# Sharp_IR_Distance_2YA02.net
KiCad netlist of a schematic drawn in EAGLE
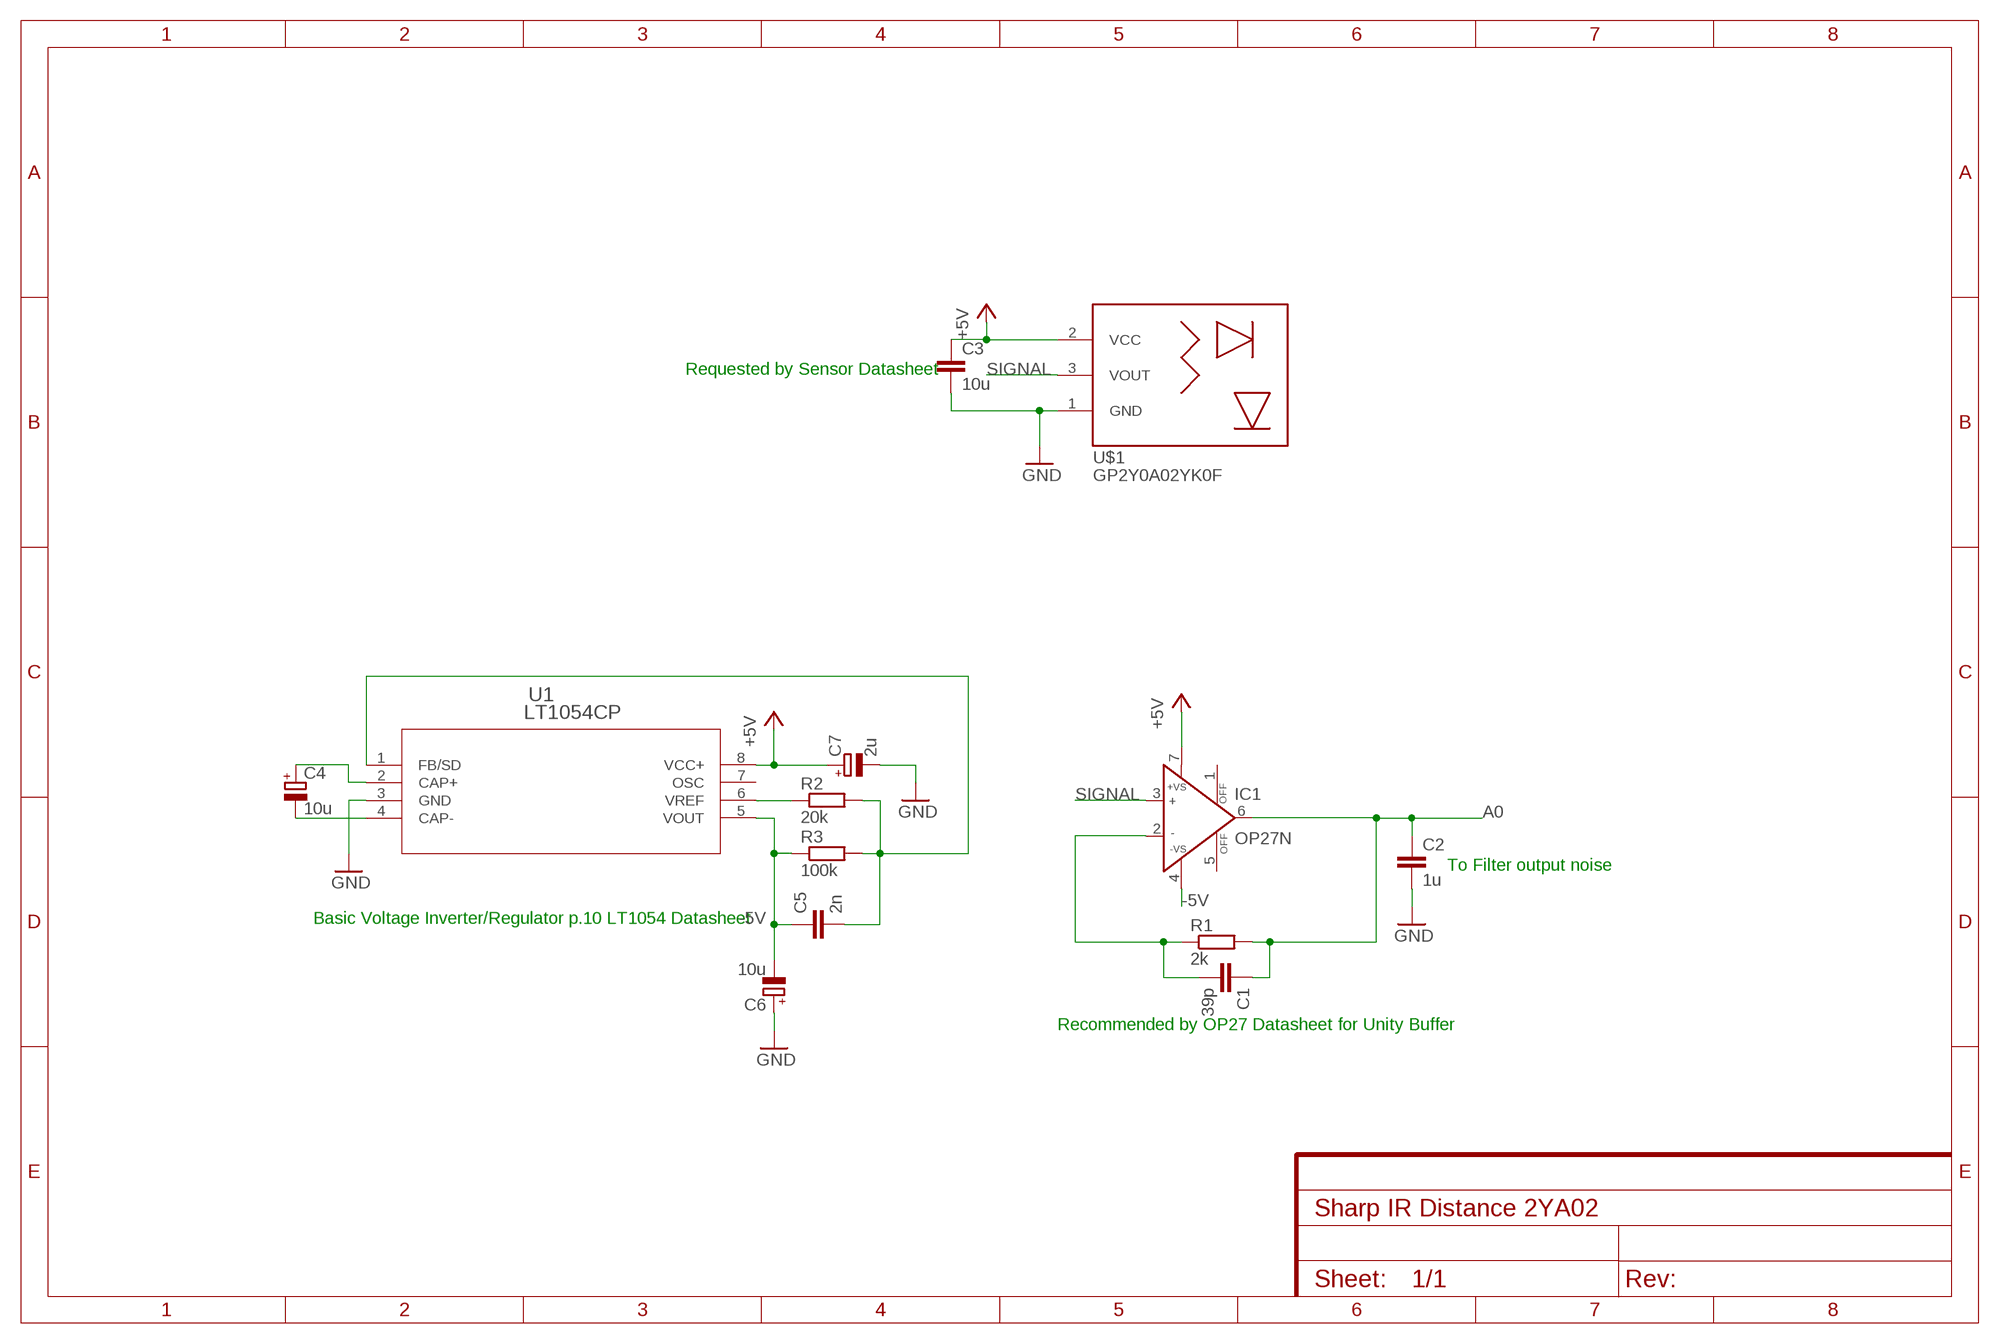
[diagram p0: schematic, sheet 1]

(export (version "E")
  (design (tool "Eeschema 10.0.6"))
  (components
    (comp (ref "C1")
      (value "39p")
      (footprint "eagle-import:C025-024X044")
      (libsource (lib "eagle-import") (part "C-EU025-024X044"))
    )
    (comp (ref "C2")
      (value "1u")
      (footprint "eagle-import:C025-024X044")
      (libsource (lib "eagle-import") (part "C-EU025-024X044"))
    )
    (comp (ref "C3")
      (value "10u")
      (footprint "eagle-import:C025-024X044")
      (libsource (lib "eagle-import") (part "C-EU025-024X044"))
    )
    (comp (ref "C4")
      (value "10u")
      (footprint "eagle-import:TT2D5")
      (libsource (lib "eagle-import") (part "CPOL-EUTT2D5"))
    )
    (comp (ref "C5")
      (value "2n")
      (footprint "eagle-import:C025-024X044")
      (libsource (lib "eagle-import") (part "C-EU025-024X044"))
    )
    (comp (ref "C6")
      (value "10u")
      (footprint "eagle-import:TT2D5")
      (libsource (lib "eagle-import") (part "CPOL-EUTT2D5"))
    )
    (comp (ref "C7")
      (value "2u")
      (footprint "eagle-import:TT2D5")
      (libsource (lib "eagle-import") (part "CPOL-EUTT2D5"))
    )
    (comp (ref "IC1")
      (value "OP27N")
      (footprint "eagle-import:DIL08")
      (libsource (lib "eagle-import") (part "OP27N"))
    )
    (comp (ref "R1")
      (value "2k")
      (footprint "eagle-import:0204_7")
      (libsource (lib "eagle-import") (part "R-EU_0204/7"))
    )
    (comp (ref "R2")
      (value "20k")
      (footprint "eagle-import:0204_7")
      (libsource (lib "eagle-import") (part "IDP_library_38939663_R-EU_0204/7"))
    )
    (comp (ref "R3")
      (value "100k")
      (footprint "eagle-import:0204_7")
      (libsource (lib "eagle-import") (part "IDP_library_38939663_R-EU_0204/7"))
    )
    (comp (ref "U$1")
      (value "GP2Y0A02YK0F")
      (footprint "eagle-import:22-23-2031")
      (libsource (lib "eagle-import") (part "GP2Y0A02YK0F"))
    )
    (comp (ref "U1")
      (value "LT1054CP")
      (footprint "eagle-import:P8")
      (fields (field (name "COPYRIGHT") "Copyright (C) 2023 Ultra Librarian. All rights reserved."))
      (libsource (lib "eagle-import") (part "LT1054CP"))
    )
  )
  (nets
    (net (code "1") (name "+5V") (class "Default")
      (node (ref "C3") (pin "1") (pinfunction "1_1") (pintype "passive"))
      (node (ref "C7") (pin "+") (pinfunction "+_+") (pintype "passive"))
      (node (ref "IC1") (pin "7") (pinfunction "+VS_7") (pintype "input"))
      (node (ref "U$1") (pin "2") (pinfunction "VCC_2") (pintype "bidirectional"))
      (node (ref "U1") (pin "8") (pinfunction "VCC+_8") (pintype "power_in"))
    )
    (net (code "2") (name "/-5V") (class "Default")
      (node (ref "C5") (pin "1") (pinfunction "1_1") (pintype "passive"))
      (node (ref "C6") (pin "-") (pinfunction "-_-") (pintype "passive"))
      (node (ref "IC1") (pin "4") (pinfunction "-VS_4") (pintype "input"))
      (node (ref "R3") (pin "1") (pinfunction "1_1") (pintype "passive"))
      (node (ref "U1") (pin "5") (pinfunction "VOUT_5") (pintype "output"))
    )
    (net (code "3") (name "/A0") (class "Default")
      (node (ref "C1") (pin "1") (pinfunction "1_1") (pintype "passive"))
      (node (ref "C2") (pin "1") (pinfunction "1_1") (pintype "passive"))
      (node (ref "IC1") (pin "6") (pinfunction "OUT_6") (pintype "output"))
      (node (ref "R1") (pin "2") (pinfunction "2_2") (pintype "passive"))
    )
    (net (code "4") (name "/SIGNAL") (class "Default")
      (node (ref "IC1") (pin "3") (pinfunction "IN+_3") (pintype "input"))
      (node (ref "U$1") (pin "3") (pinfunction "VOUT_3") (pintype "bidirectional"))
    )
    (net (code "5") (name "GND") (class "Default")
      (node (ref "C2") (pin "2") (pinfunction "2_2") (pintype "passive"))
      (node (ref "C3") (pin "2") (pinfunction "2_2") (pintype "passive"))
      (node (ref "C6") (pin "+") (pinfunction "+_+") (pintype "passive"))
      (node (ref "C7") (pin "-") (pinfunction "-_-") (pintype "passive"))
      (node (ref "U$1") (pin "1") (pinfunction "GND_1") (pintype "bidirectional"))
      (node (ref "U1") (pin "3") (pinfunction "GND_3") (pintype "power_in"))
    )
    (net (code "6") (name "Net-(IC1-IN-)") (class "Default")
      (node (ref "C1") (pin "2") (pinfunction "2_2") (pintype "passive"))
      (node (ref "IC1") (pin "2") (pinfunction "IN-_2") (pintype "input"))
      (node (ref "R1") (pin "1") (pinfunction "1_1") (pintype "passive"))
    )
    (net (code "7") (name "Net-(U1-CAP+)") (class "Default")
      (node (ref "C4") (pin "+") (pinfunction "+_+") (pintype "passive"))
      (node (ref "U1") (pin "2") (pinfunction "CAP+_2") (pintype "passive"))
    )
    (net (code "8") (name "Net-(U1-CAP-)") (class "Default")
      (node (ref "C4") (pin "-") (pinfunction "-_-") (pintype "passive"))
      (node (ref "U1") (pin "4") (pinfunction "CAP-_4") (pintype "passive"))
    )
    (net (code "9") (name "Net-(U1-FB{slash}SD)") (class "Default")
      (node (ref "C5") (pin "2") (pinfunction "2_2") (pintype "passive"))
      (node (ref "R2") (pin "2") (pinfunction "2_2") (pintype "passive"))
      (node (ref "R3") (pin "2") (pinfunction "2_2") (pintype "passive"))
      (node (ref "U1") (pin "1") (pinfunction "FB/SD_1") (pintype "input"))
    )
    (net (code "10") (name "Net-(U1-VREF)") (class "Default")
      (node (ref "R2") (pin "1") (pinfunction "1_1") (pintype "passive"))
      (node (ref "U1") (pin "6") (pinfunction "VREF_6") (pintype "passive"))
    )
    (net (code "11") (name "unconnected-(IC1-OFF-Pad1)") (class "Default")
      (node (ref "IC1") (pin "1") (pinfunction "OFF_1") (pintype "passive"))
    )
    (net (code "12") (name "unconnected-(IC1-OFF-Pad5)") (class "Default")
      (node (ref "IC1") (pin "5") (pinfunction "OFF_5") (pintype "passive"))
    )
    (net (code "13") (name "unconnected-(U1-OSC-Pad7)") (class "Default")
      (node (ref "U1") (pin "7") (pinfunction "OSC_7") (pintype "input"))
    )
  )
)
